# emonBuck_v0_3.net
KiCad netlist of a schematic drawn in EAGLE
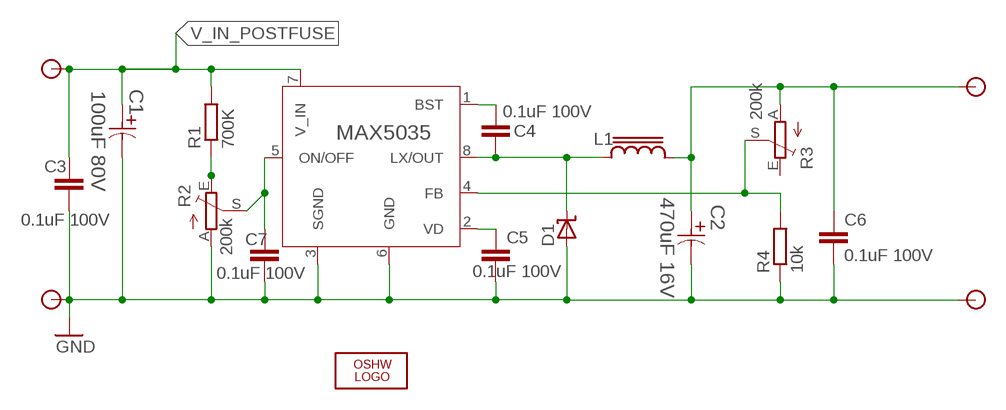
[diagram p0: schematic, sheet 1]

(export (version "E")
  (design (tool "Eeschema 10.0.6"))
  (components
    (comp (ref "C1")
      (value "100uF 80V")
      (footprint "eagle-import:CAPAE1350X1400N")
      (fields (field (name "MPN") "EEVFK1K101Q") (field (name "TOLERANCE") "±20 %"))
      (libsource (lib "eagle-import") (part "EEV--CASE-H13FK1K101Q"))
    )
    (comp (ref "C2")
      (value "470uF 16V")
      (footprint "eagle-import:CAPAE830X1050N")
      (fields (field (name "MPN") "EEE-FK1C471P") (field (name "TOLERANCE") "±20 %"))
      (libsource (lib "eagle-import") (part "EEE--CASE-FFK1C471P"))
    )
    (comp (ref "C3")
      (value "0.1uF 100V")
      (footprint "eagle-import:C0603")
      (libsource (lib "eagle-import") (part "C-EUC0603"))
    )
    (comp (ref "C4")
      (value "0.1uF 100V")
      (footprint "eagle-import:C0603")
      (libsource (lib "eagle-import") (part "C-EUC0603"))
    )
    (comp (ref "C5")
      (value "0.1uF 100V")
      (footprint "eagle-import:C0603")
      (libsource (lib "eagle-import") (part "C-EUC0603"))
    )
    (comp (ref "C6")
      (value "0.1uF 100V")
      (footprint "eagle-import:C0603")
      (libsource (lib "eagle-import") (part "C-EUC0603"))
    )
    (comp (ref "C7")
      (value "0.1uF 100V")
      (footprint "eagle-import:C0603")
      (libsource (lib "eagle-import") (part "C-EUC0603"))
    )
    (comp (ref "D1")
      (value "MBRS1100T3G")
      (footprint "eagle-import:SMB_1")
      (libsource (lib "eagle-import") (part "MBRS1100T3G"))
    )
    (comp (ref "L1")
      (value "SRR1208")
      (footprint "eagle-import:SSR1208")
      (fields (field (name "MPN") "SRR1208-151YL"))
      (libsource (lib "eagle-import") (part "SRR1208"))
    )
    (comp (ref "LOGO1")
      (value "OSHW_LOGO_6MILX0200-NT")
      (footprint "eagle-import:OSHW_6X200_NOTEXT")
      (libsource (lib "eagle-import") (part "OSHW_LOGO_6MILX0200-NT"))
    )
    (comp (ref "MAX5035")
      (value "MAX5035")
      (footprint "eagle-import:21-0111D_SBE-14")
      (fields (field (name "MPN") "MAX5035EASA+"))
      (libsource (lib "eagle-import") (part "MAX5035"))
    )
    (comp (ref "R1")
      (value "700K")
      (footprint "eagle-import:R0603")
      (libsource (lib "eagle-import") (part "R-EU_R0603"))
    )
    (comp (ref "R2")
      (value "200k")
      (footprint "eagle-import:B64W")
      (libsource (lib "eagle-import") (part "TRIM_EU-B64W"))
    )
    (comp (ref "R3")
      (value "200k")
      (footprint "eagle-import:B64W")
      (libsource (lib "eagle-import") (part "TRIM_EU-B64W"))
    )
    (comp (ref "R4")
      (value "10k")
      (footprint "eagle-import:R0603")
      (libsource (lib "eagle-import") (part "R-EU_R0603"))
    )
    (comp (ref "U$1")
      (value "TP0.8MM")
      (footprint "eagle-import:TP0.8")
      (libsource (lib "eagle-import") (part "TP0.8MM"))
    )
    (comp (ref "U$2")
      (value "TP0.8MM")
      (footprint "eagle-import:TP0.8")
      (libsource (lib "eagle-import") (part "TP0.8MM"))
    )
    (comp (ref "U$3")
      (value "TP0.8MM")
      (footprint "eagle-import:TP0.8")
      (libsource (lib "eagle-import") (part "TP0.8MM"))
    )
    (comp (ref "U$4")
      (value "TP0.8MM")
      (footprint "eagle-import:TP0.8")
      (libsource (lib "eagle-import") (part "TP0.8MM"))
    )
  )
  (nets
    (net (code "1") (name "GND") (class "Default")
      (node (ref "C1") (pin "2") (pinfunction "2_2") (pintype "passive"))
      (node (ref "C2") (pin "2") (pinfunction "2_2") (pintype "passive"))
      (node (ref "C3") (pin "2") (pinfunction "2_2") (pintype "passive"))
      (node (ref "C5") (pin "2") (pinfunction "2_2") (pintype "passive"))
      (node (ref "C6") (pin "2") (pinfunction "2_2") (pintype "passive"))
      (node (ref "C7") (pin "2") (pinfunction "2_2") (pintype "passive"))
      (node (ref "D1") (pin "A") (pinfunction "A_A") (pintype "passive"))
      (node (ref "MAX5035") (pin "3") (pinfunction "SGND_3") (pintype "power_in"))
      (node (ref "MAX5035") (pin "6") (pinfunction "GND_6") (pintype "passive"))
      (node (ref "R2") (pin "A") (pinfunction "A_A") (pintype "passive"))
      (node (ref "R4") (pin "1") (pinfunction "1_1") (pintype "passive"))
      (node (ref "U$2") (pin "P$1") (pinfunction "P$1_P$1") (pintype "bidirectional"))
      (node (ref "U$4") (pin "P$1") (pinfunction "P$1_P$1") (pintype "bidirectional"))
    )
    (net (code "2") (name "Net-(C2-Pad1)") (class "Default")
      (node (ref "C2") (pin "1") (pinfunction "1_1") (pintype "passive"))
      (node (ref "C6") (pin "1") (pinfunction "1_1") (pintype "passive"))
      (node (ref "L1") (pin "2") (pinfunction "2_2") (pintype "passive"))
      (node (ref "R3") (pin "A") (pinfunction "A_A") (pintype "passive"))
      (node (ref "U$3") (pin "P$1") (pinfunction "P$1_P$1") (pintype "bidirectional"))
    )
    (net (code "3") (name "Net-(MAX5035-BST)") (class "Default")
      (node (ref "C4") (pin "1") (pinfunction "1_1") (pintype "passive"))
      (node (ref "MAX5035") (pin "1") (pinfunction "BST_1") (pintype "passive"))
    )
    (net (code "4") (name "Net-(MAX5035-FB)") (class "Default")
      (node (ref "MAX5035") (pin "4") (pinfunction "FB_4") (pintype "input"))
      (node (ref "R3") (pin "S") (pinfunction "S_S") (pintype "passive"))
      (node (ref "R4") (pin "2") (pinfunction "2_2") (pintype "passive"))
    )
    (net (code "5") (name "Net-(MAX5035-LX{slash}OUT)") (class "Default")
      (node (ref "C4") (pin "2") (pinfunction "2_2") (pintype "passive"))
      (node (ref "D1") (pin "C") (pinfunction "C_C") (pintype "passive"))
      (node (ref "L1") (pin "1") (pinfunction "1_1") (pintype "passive"))
      (node (ref "MAX5035") (pin "8") (pinfunction "LX/OUT_8") (pintype "output"))
    )
    (net (code "6") (name "Net-(MAX5035-ON{slash}OFF)") (class "Default")
      (node (ref "C7") (pin "1") (pinfunction "1_1") (pintype "passive"))
      (node (ref "MAX5035") (pin "5") (pinfunction "ON/OFF_5") (pintype "input"))
      (node (ref "R2") (pin "S") (pinfunction "S_S") (pintype "passive"))
    )
    (net (code "7") (name "Net-(MAX5035-VD)") (class "Default")
      (node (ref "C5") (pin "1") (pinfunction "1_1") (pintype "passive"))
      (node (ref "MAX5035") (pin "2") (pinfunction "VD_2") (pintype "input"))
    )
    (net (code "8") (name "Net-(R1-Pad1)") (class "Default")
      (node (ref "R1") (pin "1") (pinfunction "1_1") (pintype "passive"))
      (node (ref "R2") (pin "E") (pinfunction "E_E") (pintype "passive"))
    )
    (net (code "9") (name "V_IN_POSTFUSE") (class "Default")
      (node (ref "C1") (pin "1") (pinfunction "1_1") (pintype "passive"))
      (node (ref "C3") (pin "1") (pinfunction "1_1") (pintype "passive"))
      (node (ref "MAX5035") (pin "7") (pinfunction "V_IN_7") (pintype "power_in"))
      (node (ref "R1") (pin "2") (pinfunction "2_2") (pintype "passive"))
      (node (ref "U$1") (pin "P$1") (pinfunction "P$1_P$1") (pintype "bidirectional"))
    )
    (net (code "10") (name "unconnected-(R3-PadE)") (class "Default")
      (node (ref "R3") (pin "E") (pinfunction "E_E") (pintype "passive"))
    )
  )
)
